# CPCIS_EEM_Controller.net
KiCad netlist of a schematic drawn in Altium Designer
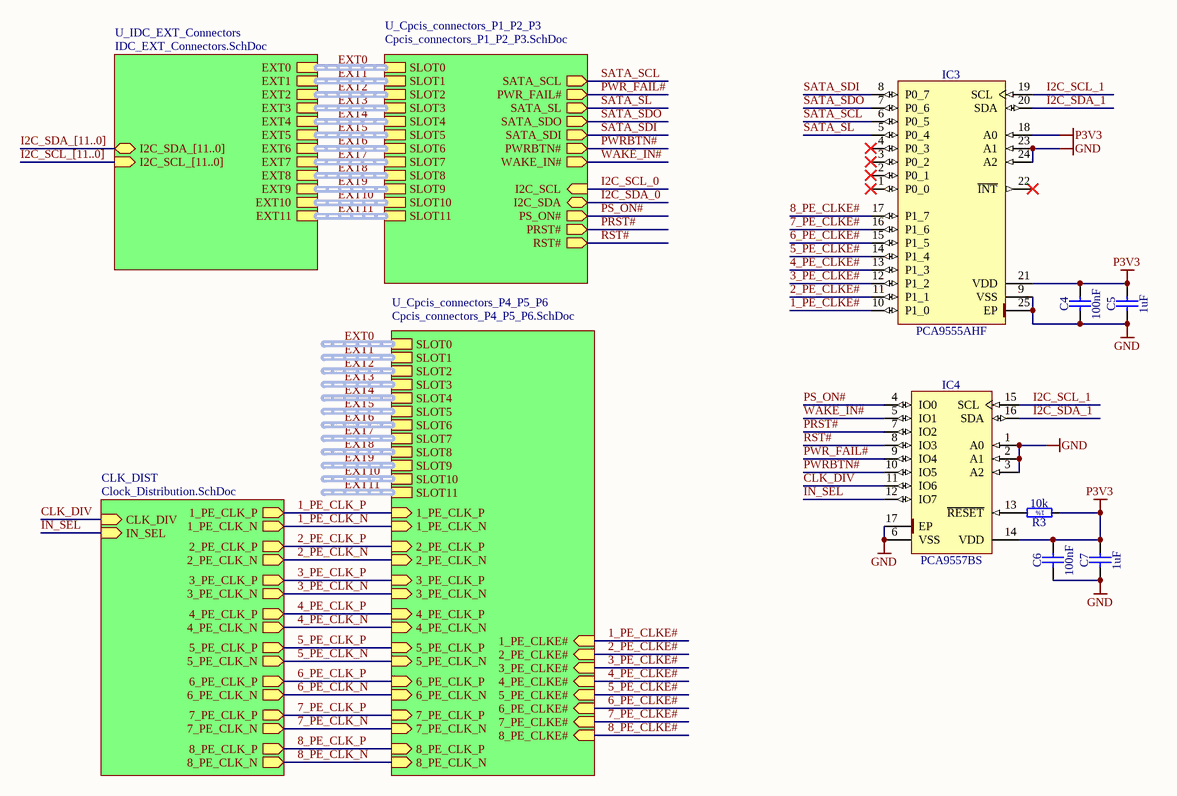
[diagram p0: CPCIS_EEM_Controller.SchDoc]

(export (version "E")
  (design (tool "Eeschema 10.0.6"))
  (components
    (comp (ref "C4")
      (value "100nF")
      (footprint "CAPC0603X33N")
      (description "Non-polarised capacitor")
      (fields
        (field (name "PART NUMBER") "CC0201_100NF_6.3V_10%_X5R")
        (field (name "VOLTAGE") "6.3V")
        (field (name "AUTHOR") "CERN DEM JLC")
      )
      (libsource (lib "Capacitors") (part "Capacitor - non polarized"))
    )
    (comp (ref "C5")
      (value "1uF")
      (footprint "CAPC1608X87N")
      (description "Non-polarised capacitor")
      (fields
        (field (name "PART NUMBER") "CC0603_1UF_25V_10%_X7R")
        (field (name "VOLTAGE") "25V")
        (field (name "AUTHOR") "CERN DEM JLC")
      )
      (libsource (lib "Capacitors") (part "Capacitor - non polarized"))
    )
    (comp (ref "C6")
      (value "100nF")
      (footprint "CAPC0603X33N")
      (description "Non-polarised capacitor")
      (fields
        (field (name "PART NUMBER") "CC0201_100NF_6.3V_10%_X5R")
        (field (name "VOLTAGE") "6.3V")
        (field (name "AUTHOR") "CERN DEM JLC")
      )
      (libsource (lib "Capacitors") (part "Capacitor - non polarized"))
    )
    (comp (ref "C7")
      (value "1uF")
      (footprint "CAPC1608X87N")
      (description "Non-polarised capacitor")
      (fields
        (field (name "PART NUMBER") "CC0603_1UF_25V_10%_X7R")
        (field (name "VOLTAGE") "25V")
        (field (name "AUTHOR") "CERN DEM JLC")
      )
      (libsource (lib "Capacitors") (part "Capacitor - non polarized"))
    )
    (comp (ref "IC3")
      (value "PCA9555AHF")
      (footprint "QFN50P400X400X80-25N-S225")
      (description "Low-Voltage 16-Bit I2C-bus I/O Port With Interrupt and Weak Pull-Up")
      (fields (field (name "MANUFACTURER") "NXP SEMICONDUCTORS") (field (name "AUTHOR") "CERN DEM BC"))
      (libsource (lib "ICs And Semiconductors") (part "PCA9555AHF"))
    )
    (comp (ref "IC4")
      (value "PCA9557BS")
      (footprint "QFN65P400X400X100-17N-S225")
      (description "8-Bit I2C-bus and SMBus I/O Port with Reset")
      (fields (field (name "MANUFACTURER") "NXP SEMICONDUCTORS") (field (name "AUTHOR") "CERN DEM JMW"))
      (libsource (lib "ICs And Semiconductors") (part "PCA9557BS"))
    )
    (comp (ref "R3")
      (value "10k")
      (footprint "RESC1005X40N")
      (description "Resistor - 1%")
      (fields
        (field (name "PART NUMBER") "R0402_10K_1%_0.0625W_100PPM")
        (field (name "POWER") "0.0625W")
        (field (name "AUTHOR") "CERN DEM JLC")
      )
      (libsource (lib "Resistors") (part "Resistor - 1%"))
    )
  )
  (nets
    (net (code "33") (name "/1_PE_CLKE#") (class "Default")
      (node (ref "IC3") (pin "10") (pinfunction "P1_0_10") (pintype "bidirectional"))
    )
    (net (code "36") (name "/2_PE_CLKE#") (class "Default")
      (node (ref "IC3") (pin "11") (pinfunction "P1_1_11") (pintype "bidirectional"))
    )
    (net (code "39") (name "/3_PE_CLKE#") (class "Default")
      (node (ref "IC3") (pin "12") (pinfunction "P1_2_12") (pintype "bidirectional"))
    )
    (net (code "42") (name "/4_PE_CLKE#") (class "Default")
      (node (ref "IC3") (pin "13") (pinfunction "P1_3_13") (pintype "bidirectional"))
    )
    (net (code "45") (name "/5_PE_CLKE#") (class "Default")
      (node (ref "IC3") (pin "14") (pinfunction "P1_4_14") (pintype "bidirectional"))
    )
    (net (code "48") (name "/6_PE_CLKE#") (class "Default")
      (node (ref "IC3") (pin "15") (pinfunction "P1_5_15") (pintype "bidirectional"))
    )
    (net (code "51") (name "/7_PE_CLKE#") (class "Default")
      (node (ref "IC3") (pin "16") (pinfunction "P1_6_16") (pintype "bidirectional"))
    )
    (net (code "54") (name "/8_PE_CLKE#") (class "Default")
      (node (ref "IC3") (pin "17") (pinfunction "P1_7_17") (pintype "bidirectional"))
    )
    (net (code "57") (name "/CLK_DIV") (class "Default")
      (node (ref "IC4") (pin "11") (pinfunction "IO6_11") (pintype "bidirectional"))
    )
    (net (code "59") (name "/I2C_SCL_1") (class "Default")
      (node (ref "IC3") (pin "19") (pinfunction "SCL_19") (pintype "input"))
      (node (ref "IC4") (pin "15") (pinfunction "SCL_15") (pintype "input"))
    )
    (net (code "62") (name "/I2C_SDA_1") (class "Default")
      (node (ref "IC3") (pin "20") (pinfunction "SDA_20") (pintype "bidirectional"))
      (node (ref "IC4") (pin "16") (pinfunction "SDA_16") (pintype "bidirectional"))
    )
    (net (code "64") (name "/IN_SEL") (class "Default")
      (node (ref "IC4") (pin "12") (pinfunction "IO7_12") (pintype "bidirectional"))
    )
    (net (code "65") (name "/PRST#") (class "Default")
      (node (ref "IC4") (pin "7") (pinfunction "IO2_7") (pintype "bidirectional"))
    )
    (net (code "66") (name "/PS_ON#") (class "Default")
      (node (ref "IC4") (pin "4") (pinfunction "IO0_4") (pintype "bidirectional"))
    )
    (net (code "67") (name "/PWRBTN#") (class "Default")
      (node (ref "IC4") (pin "10") (pinfunction "IO5_10") (pintype "bidirectional"))
    )
    (net (code "68") (name "/PWR_FAIL#") (class "Default")
      (node (ref "IC4") (pin "9") (pinfunction "IO4_9") (pintype "bidirectional"))
    )
    (net (code "69") (name "/RST#") (class "Default")
      (node (ref "IC4") (pin "8") (pinfunction "IO3_8") (pintype "bidirectional"))
    )
    (net (code "70") (name "/SATA_SCL") (class "Default")
      (node (ref "IC3") (pin "6") (pinfunction "P0_5_6") (pintype "bidirectional"))
    )
    (net (code "71") (name "/SATA_SDI") (class "Default")
      (node (ref "IC3") (pin "8") (pinfunction "P0_7_8") (pintype "bidirectional"))
    )
    (net (code "72") (name "/SATA_SDO") (class "Default")
      (node (ref "IC3") (pin "7") (pinfunction "P0_6_7") (pintype "bidirectional"))
    )
    (net (code "73") (name "/SATA_SL") (class "Default")
      (node (ref "IC3") (pin "5") (pinfunction "P0_4_5") (pintype "bidirectional"))
    )
    (net (code "74") (name "/WAKE_IN#") (class "Default")
      (node (ref "IC4") (pin "5") (pinfunction "IO1_5") (pintype "bidirectional"))
    )
    (net (code "87") (name "GND") (class "Default")
      (node (ref "C4") (pin "1") (pinfunction "1_1") (pintype "passive"))
      (node (ref "C5") (pin "1") (pinfunction "1_1") (pintype "passive"))
      (node (ref "C6") (pin "1") (pinfunction "1_1") (pintype "passive"))
      (node (ref "C7") (pin "1") (pinfunction "1_1") (pintype "passive"))
      (node (ref "IC3") (pin "23") (pinfunction "A1_23") (pintype "input"))
      (node (ref "IC3") (pin "24") (pinfunction "A2_24") (pintype "input"))
      (node (ref "IC3") (pin "25") (pinfunction "EP_25") (pintype "power_in"))
      (node (ref "IC3") (pin "9") (pinfunction "VSS_9") (pintype "power_in"))
      (node (ref "IC4") (pin "1") (pinfunction "A0_1") (pintype "input"))
      (node (ref "IC4") (pin "17") (pinfunction "EP_17") (pintype "power_in"))
      (node (ref "IC4") (pin "2") (pinfunction "A1_2") (pintype "input"))
      (node (ref "IC4") (pin "3") (pinfunction "A2_3") (pintype "input"))
      (node (ref "IC4") (pin "6") (pinfunction "VSS_6") (pintype "power_in"))
    )
    (net (code "88") (name "Net-(IC4-~{RESET})") (class "Default")
      (node (ref "IC4") (pin "13") (pinfunction "~{RESET}_13") (pintype "input"))
      (node (ref "R3") (pin "2") (pinfunction "2_2") (pintype "passive"))
    )
    (net (code "89") (name "P3V3") (class "Default")
      (node (ref "C4") (pin "2") (pinfunction "2_2") (pintype "passive"))
      (node (ref "C5") (pin "2") (pinfunction "2_2") (pintype "passive"))
      (node (ref "C6") (pin "2") (pinfunction "2_2") (pintype "passive"))
      (node (ref "C7") (pin "2") (pinfunction "2_2") (pintype "passive"))
      (node (ref "IC3") (pin "18") (pinfunction "A0_18") (pintype "input"))
      (node (ref "IC3") (pin "21") (pinfunction "VDD_21") (pintype "power_in"))
      (node (ref "IC4") (pin "14") (pinfunction "VDD_14") (pintype "power_in"))
      (node (ref "R3") (pin "1") (pinfunction "1_1") (pintype "passive"))
    )
    (net (code "90") (name "unconnected-(IC3-P0_0-Pad1)") (class "Default")
      (node (ref "IC3") (pin "1") (pinfunction "P0_0_1") (pintype "bidirectional+no_connect"))
    )
    (net (code "91") (name "unconnected-(IC3-P0_1-Pad2)") (class "Default")
      (node (ref "IC3") (pin "2") (pinfunction "P0_1_2") (pintype "bidirectional+no_connect"))
    )
    (net (code "92") (name "unconnected-(IC3-P0_2-Pad3)") (class "Default")
      (node (ref "IC3") (pin "3") (pinfunction "P0_2_3") (pintype "bidirectional+no_connect"))
    )
    (net (code "93") (name "unconnected-(IC3-P0_3-Pad4)") (class "Default")
      (node (ref "IC3") (pin "4") (pinfunction "P0_3_4") (pintype "bidirectional+no_connect"))
    )
    (net (code "94") (name "unconnected-(IC3-~{INT}-Pad22)") (class "Default")
      (node (ref "IC3") (pin "22") (pinfunction "~{INT}_22") (pintype "output+no_connect"))
    )
  )
)
